# digital_host_for_ADS1216_SPI_connecor_to.net
KiCad netlist of a schematic drawn in Altium Designer
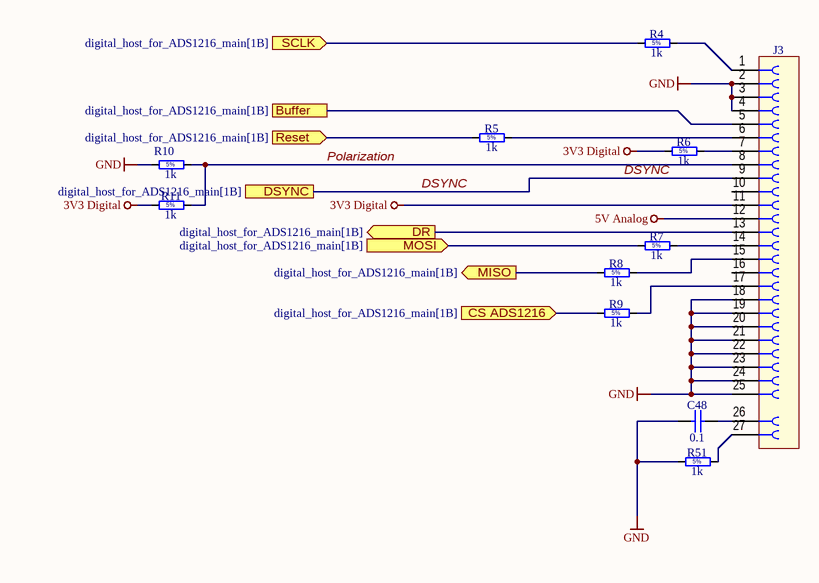
[diagram p0: digital_host_for_ADS1216_SPI_connecor_to_ADS1216.SchDoc]

(export (version "E")
  (design (tool "Eeschema 10.0.6"))
  (components
    (comp (ref "C48")
      (value "0.1")
      (footprint "CAPC2012X90N")
      (description "Non-polarised capacitor2012")
      (libsource (lib "schematic_hall_library") (part "Capacitor - non polarized"))
    )
    (comp (ref "J3")
      (value "~")
      (footprint "footprint_library:TYCO_3-1634586-2")
      (description "Connector 25 Female")
      (libsource (lib "first_scheme.~(65)") (part "Connector 25 Female"))
    )
    (comp (ref "R4")
      (value "1k")
      (footprint "RESC2012X70N")
      (description "Resistor - 5%")
      (fields (field (name "TOLERANCE") "5%"))
      (libsource (lib "first_scheme.~(65)") (part "Resistor - 5%"))
    )
    (comp (ref "R5")
      (value "1k")
      (footprint "RESC2012X70N")
      (description "Resistor - 5%")
      (fields (field (name "TOLERANCE") "5%"))
      (libsource (lib "first_scheme.~(65)") (part "Resistor - 5%"))
    )
    (comp (ref "R6")
      (value "1k")
      (footprint "RESC2012X70N")
      (description "Resistor - 5%")
      (fields (field (name "TOLERANCE") "5%"))
      (libsource (lib "first_scheme.~(65)") (part "Resistor - 5%"))
    )
    (comp (ref "R7")
      (value "1k")
      (footprint "RESC2012X70N")
      (description "Resistor - 5%")
      (fields (field (name "TOLERANCE") "5%"))
      (libsource (lib "first_scheme.~(65)") (part "Resistor - 5%"))
    )
    (comp (ref "R8")
      (value "1k")
      (footprint "RESC2012X70N")
      (description "Resistor - 5%")
      (fields (field (name "TOLERANCE") "5%"))
      (libsource (lib "first_scheme.~(65)") (part "Resistor - 5%"))
    )
    (comp (ref "R9")
      (value "1k")
      (footprint "RESC2012X70N")
      (description "Resistor - 5%")
      (fields (field (name "TOLERANCE") "5%"))
      (libsource (lib "first_scheme.~(65)") (part "Resistor - 5%"))
    )
    (comp (ref "R10")
      (value "1k")
      (footprint "RESC2012X70N")
      (description "Resistor - 5%")
      (fields (field (name "TOLERANCE") "5%"))
      (libsource (lib "first_scheme.~(65)") (part "Resistor - 5%"))
    )
    (comp (ref "R11")
      (value "1k")
      (footprint "RESC2012X70N")
      (description "Resistor - 5%")
      (fields (field (name "TOLERANCE") "5%"))
      (libsource (lib "first_scheme.~(65)") (part "Resistor - 5%"))
    )
    (comp (ref "R51")
      (value "1k")
      (footprint "RESC2012X70N")
      (description "Resistor - 5%")
      (fields (field (name "TOLERANCE") "5%"))
      (libsource (lib "Integrated_Library1") (part "Resistor - 5%"))
    )
  )
  (nets
    (net (code "1") (name "/Buffer") (class "Default")
      (node (ref "J3") (pin "5") (pinfunction "5_5") (pintype "passive"))
    )
    (net (code "2") (name "/CS ADS1216") (class "Default")
      (node (ref "R9") (pin "1") (pinfunction "1_1") (pintype "passive"))
    )
    (net (code "3") (name "/DR") (class "Default")
      (node (ref "J3") (pin "13") (pinfunction "13_13") (pintype "passive"))
    )
    (net (code "4") (name "/DSYNC") (class "Default")
      (node (ref "J3") (pin "9") (pinfunction "9_9") (pintype "passive"))
    )
    (net (code "5") (name "/MISO") (class "Default")
      (node (ref "R8") (pin "1") (pinfunction "1_1") (pintype "passive"))
    )
    (net (code "6") (name "/MOSI") (class "Default")
      (node (ref "R7") (pin "1") (pinfunction "1_1") (pintype "passive"))
    )
    (net (code "7") (name "/Polarization") (class "Default")
      (node (ref "J3") (pin "8") (pinfunction "8_8") (pintype "passive"))
      (node (ref "R10") (pin "1") (pinfunction "1_1") (pintype "passive"))
      (node (ref "R11") (pin "1") (pinfunction "1_1") (pintype "passive"))
    )
    (net (code "8") (name "/Reset") (class "Default")
      (node (ref "R5") (pin "1") (pinfunction "1_1") (pintype "passive"))
    )
    (net (code "9") (name "/SCLK") (class "Default")
      (node (ref "R4") (pin "1") (pinfunction "1_1") (pintype "passive"))
    )
    (net (code "10") (name "3V3 Digital") (class "Default")
      (node (ref "J3") (pin "11") (pinfunction "11_11") (pintype "passive"))
      (node (ref "R11") (pin "2") (pinfunction "2_2") (pintype "passive"))
      (node (ref "R6") (pin "1") (pinfunction "1_1") (pintype "passive"))
    )
    (net (code "11") (name "5V Analog") (class "Default")
      (node (ref "J3") (pin "12") (pinfunction "12_12") (pintype "passive"))
    )
    (net (code "12") (name "GND") (class "Default")
      (node (ref "C48") (pin "1") (pinfunction "1_1") (pintype "passive"))
      (node (ref "J3") (pin "18") (pinfunction "18_18") (pintype "passive"))
      (node (ref "J3") (pin "19") (pinfunction "19_19") (pintype "passive"))
      (node (ref "J3") (pin "2") (pinfunction "2_2") (pintype "passive"))
      (node (ref "J3") (pin "20") (pinfunction "20_20") (pintype "passive"))
      (node (ref "J3") (pin "21") (pinfunction "21_21") (pintype "passive"))
      (node (ref "J3") (pin "22") (pinfunction "22_22") (pintype "passive"))
      (node (ref "J3") (pin "23") (pinfunction "23_23") (pintype "passive"))
      (node (ref "J3") (pin "24") (pinfunction "24_24") (pintype "passive"))
      (node (ref "J3") (pin "25") (pinfunction "25_25") (pintype "passive"))
      (node (ref "J3") (pin "3") (pinfunction "3_3") (pintype "passive"))
      (node (ref "J3") (pin "4") (pinfunction "4_4") (pintype "passive"))
      (node (ref "R10") (pin "2") (pinfunction "2_2") (pintype "passive"))
      (node (ref "R51") (pin "1") (pinfunction "1_1") (pintype "passive"))
    )
    (net (code "13") (name "Net-(C48-Pad2)") (class "Default")
      (node (ref "C48") (pin "2") (pinfunction "2_2") (pintype "passive"))
      (node (ref "J3") (pin "26") (pinfunction "26_26") (pintype "passive"))
    )
    (net (code "14") (name "Net-(J3-Pad1)") (class "Default")
      (node (ref "J3") (pin "1") (pinfunction "1_1") (pintype "passive"))
      (node (ref "R4") (pin "2") (pinfunction "2_2") (pintype "passive"))
    )
    (net (code "15") (name "Net-(J3-Pad6)") (class "Default")
      (node (ref "J3") (pin "6") (pinfunction "6_6") (pintype "passive"))
      (node (ref "R5") (pin "2") (pinfunction "2_2") (pintype "passive"))
    )
    (net (code "16") (name "Net-(J3-Pad7)") (class "Default")
      (node (ref "J3") (pin "7") (pinfunction "7_7") (pintype "passive"))
      (node (ref "R6") (pin "2") (pinfunction "2_2") (pintype "passive"))
    )
    (net (code "17") (name "Net-(J3-Pad14)") (class "Default")
      (node (ref "J3") (pin "14") (pinfunction "14_14") (pintype "passive"))
      (node (ref "R7") (pin "2") (pinfunction "2_2") (pintype "passive"))
    )
    (net (code "18") (name "Net-(J3-Pad15)") (class "Default")
      (node (ref "J3") (pin "15") (pinfunction "15_15") (pintype "passive"))
      (node (ref "R8") (pin "2") (pinfunction "2_2") (pintype "passive"))
    )
    (net (code "19") (name "Net-(J3-Pad17)") (class "Default")
      (node (ref "J3") (pin "17") (pinfunction "17_17") (pintype "passive"))
      (node (ref "R9") (pin "2") (pinfunction "2_2") (pintype "passive"))
    )
    (net (code "20") (name "Net-(J3-Pad27)") (class "Default")
      (node (ref "J3") (pin "27") (pinfunction "27_27") (pintype "passive"))
      (node (ref "R51") (pin "2") (pinfunction "2_2") (pintype "passive"))
    )
    (net (code "21") (name "unconnected-(J3-Pad10)") (class "Default")
      (node (ref "J3") (pin "10") (pinfunction "10_10") (pintype "passive"))
    )
    (net (code "22") (name "unconnected-(J3-Pad16)") (class "Default")
      (node (ref "J3") (pin "16") (pinfunction "16_16") (pintype "passive"))
    )
  )
)
